# BMS029B_Interface.net
KiCad netlist of a schematic drawn in Altium Designer
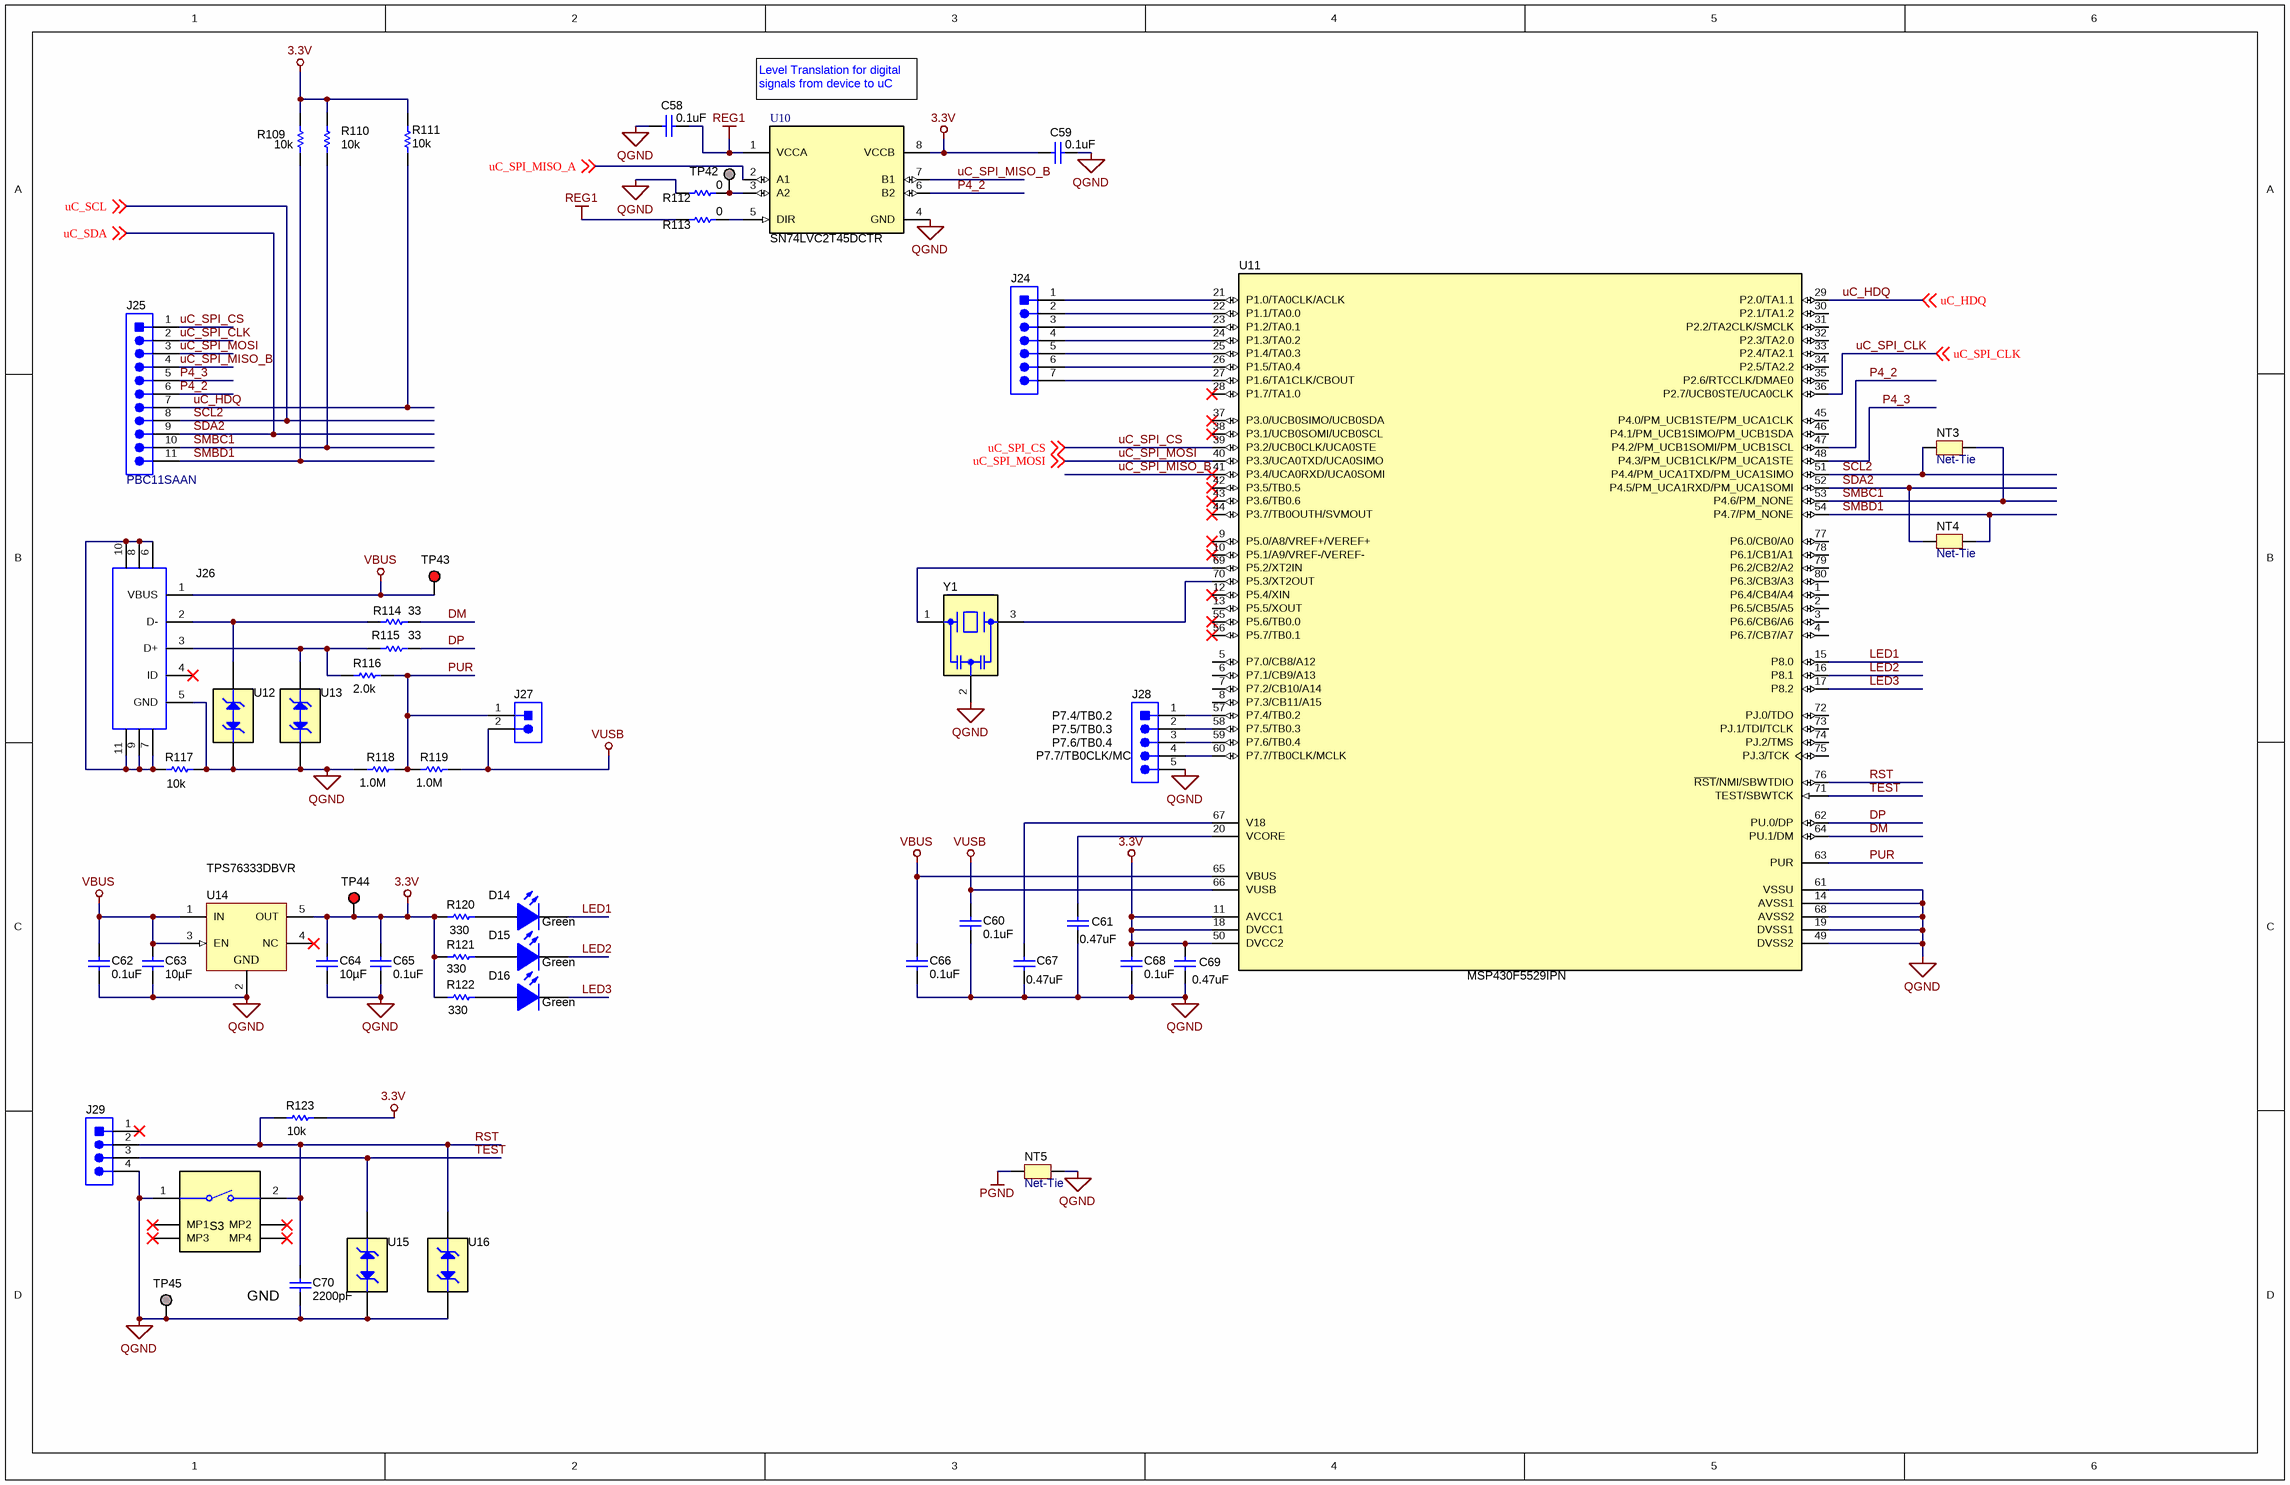
[diagram p0: BMS029B_Interface.SchDoc]

(export (version "E")
  (design (tool "Eeschema 10.0.6"))
  (components
    (comp (ref "C58")
      (value "885012205037")
      (footprint "0402")
      (description "CAP, CERM, 0.1 uF, 16 V, +/- 10%, X7R, 0402")
      (fields
        (field (name "VALUEDISPLAYED") "0.1uF")
        (field (name "MANUFACTURER") "Wurth Elektronik")
        (field (name "PUBLISHER") "Texas Instruments")
      )
      (libsource (lib "Altium Vault - TI") (part "Capacitor"))
    )
    (comp (ref "C59")
      (value "885012205037")
      (footprint "0402")
      (description "CAP, CERM, 0.1 uF, 16 V, +/- 10%, X7R, 0402")
      (fields
        (field (name "VALUEDISPLAYED") "0.1uF")
        (field (name "MANUFACTURER") "Wurth Elektronik")
        (field (name "PUBLISHER") "Texas Instruments")
      )
      (libsource (lib "Altium Vault - TI") (part "Capacitor"))
    )
    (comp (ref "C60")
      (value "885012205037")
      (footprint "0402")
      (description "CAP, CERM, 0.1 uF, 16 V, +/- 10%, X7R, 0402")
      (fields
        (field (name "VALUEDISPLAYED") "0.1uF")
        (field (name "MANUFACTURER") "Wurth Elektronik")
        (field (name "PUBLISHER") "Texas Instruments")
      )
      (libsource (lib "Altium Vault - TI") (part "Capacitor"))
    )
    (comp (ref "C61")
      (value "Capacitor")
      (footprint "0402")
      (description "CAP, CERM, 0.47 uF, 6.3 V, +/- 10%, X5R, 0402")
      (fields
        (field (name "PARTNUMBER") "04026D474KAT2A")
        (field (name "VALUEDISPLAYED") "0.47uF")
        (field (name "MANUFACTURER") "AVX")
        (field (name "PUBLISHER") "Texas Instruments")
      )
      (libsource (lib "Altium Vault - TI") (part "Capacitor"))
    )
    (comp (ref "C62")
      (value "885012205037")
      (footprint "0402")
      (description "CAP, CERM, 0.1 uF, 16 V, +/- 10%, X7R, 0402")
      (fields
        (field (name "VALUEDISPLAYED") "0.1uF")
        (field (name "MANUFACTURER") "Wurth Elektronik")
        (field (name "PUBLISHER") "Texas Instruments")
      )
      (libsource (lib "Altium Vault - TI") (part "Capacitor"))
    )
    (comp (ref "C63")
      (value "CL21A106KOQNNNG")
      (footprint "0805_HV")
      (description "CAP, CERM, 10 µF, 16 V,+/- 10%, X5R, 0805")
      (fields
        (field (name "VALUEDISPLAYED") "10µF")
        (field (name "MANUFACTURER") "Samsung Electro-Mechanics")
      )
      (libsource (lib "Altium Vault - TI") (part "Capacitor"))
    )
    (comp (ref "C64")
      (value "CL21A106KOQNNNG")
      (footprint "0805_HV")
      (description "CAP, CERM, 10 µF, 16 V,+/- 10%, X5R, 0805")
      (fields
        (field (name "VALUEDISPLAYED") "10µF")
        (field (name "MANUFACTURER") "Samsung Electro-Mechanics")
      )
      (libsource (lib "Altium Vault - TI") (part "Capacitor"))
    )
    (comp (ref "C65")
      (value "885012205037")
      (footprint "0402")
      (description "CAP, CERM, 0.1 uF, 16 V, +/- 10%, X7R, 0402")
      (fields
        (field (name "VALUEDISPLAYED") "0.1uF")
        (field (name "MANUFACTURER") "Wurth Elektronik")
        (field (name "PUBLISHER") "Texas Instruments")
      )
      (libsource (lib "Altium Vault - TI") (part "Capacitor"))
    )
    (comp (ref "C66")
      (value "885012205037")
      (footprint "0402")
      (description "CAP, CERM, 0.1 uF, 16 V, +/- 10%, X7R, 0402")
      (fields
        (field (name "VALUEDISPLAYED") "0.1uF")
        (field (name "MANUFACTURER") "Wurth Elektronik")
        (field (name "PUBLISHER") "Texas Instruments")
      )
      (libsource (lib "Altium Vault - TI") (part "Capacitor"))
    )
    (comp (ref "C67")
      (value "Capacitor")
      (footprint "0402")
      (description "CAP, CERM, 0.47 uF, 6.3 V, +/- 10%, X5R, 0402")
      (fields
        (field (name "PARTNUMBER") "04026D474KAT2A")
        (field (name "VALUEDISPLAYED") "0.47uF")
        (field (name "MANUFACTURER") "AVX")
        (field (name "PUBLISHER") "Texas Instruments")
      )
      (libsource (lib "Altium Vault - TI") (part "Capacitor"))
    )
    (comp (ref "C68")
      (value "885012205037")
      (footprint "0402")
      (description "CAP, CERM, 0.1 uF, 16 V, +/- 10%, X7R, 0402")
      (fields
        (field (name "VALUEDISPLAYED") "0.1uF")
        (field (name "MANUFACTURER") "Wurth Elektronik")
        (field (name "PUBLISHER") "Texas Instruments")
      )
      (libsource (lib "Altium Vault - TI") (part "Capacitor"))
    )
    (comp (ref "C69")
      (value "Capacitor")
      (footprint "0402")
      (description "CAP, CERM, 0.47 uF, 6.3 V, +/- 10%, X5R, 0402")
      (fields
        (field (name "PARTNUMBER") "04026D474KAT2A")
        (field (name "VALUEDISPLAYED") "0.47uF")
        (field (name "MANUFACTURER") "AVX")
        (field (name "PUBLISHER") "Texas Instruments")
      )
      (libsource (lib "Altium Vault - TI") (part "Capacitor"))
    )
    (comp (ref "C70")
      (value "885012205008")
      (footprint "0402")
      (description "CAP, CERM, 2200 pF, 10 V, +/- 10%, X7R, 0402")
      (fields
        (field (name "VALUEDISPLAYED") "2200pF")
        (field (name "MANUFACTURER") "Wurth Elektronik")
        (field (name "PUBLISHER") "Texas Instruments")
      )
      (libsource (lib "Altium Vault - TI") (part "Capacitor"))
    )
    (comp (ref "D14")
      (value "Green")
      (footprint "WL-SMCW_GREEN")
      (description "LED, Green, SMD")
      (fields (field (name "MANUFACTURER") "Wurth Elektronik") (field (name "PARTNUMBER") "150060VS75000"))
      (libsource (lib "Altium Vault - TI") (part "CMP-0002894-2"))
    )
    (comp (ref "D15")
      (value "Green")
      (footprint "WL-SMCW_GREEN")
      (description "LED, Green, SMD")
      (fields (field (name "MANUFACTURER") "Wurth Elektronik") (field (name "PARTNUMBER") "150060VS75000"))
      (libsource (lib "Altium Vault - TI") (part "CMP-0002894-2"))
    )
    (comp (ref "D16")
      (value "Green")
      (footprint "WL-SMCW_GREEN")
      (description "LED, Green, SMD")
      (fields (field (name "MANUFACTURER") "Wurth Elektronik") (field (name "PARTNUMBER") "150060VS75000"))
      (libsource (lib "Altium Vault - TI") (part "CMP-0002894-2"))
    )
    (comp (ref "J24")
      (value "PBC07SAAN")
      (footprint "Sullins_xxC07SAAN")
      (description "Header, 2.54 mm, 7x1, Gold, TH")
      (fields
        (field (name "MANUFACTURER") "Sullins Connector Solutions")
        (field (name "PUBLISHER") "Texas Instruments")
      )
      (libsource (lib "Altium Vault - TI") (part "CMP-0054584-1"))
    )
    (comp (ref "J25")
      (value "PBC11SAAN")
      (footprint "Sullins_xxC11SAAN")
      (description "Header, 2.54 mm, 11x1, Gold, TH")
      (fields
        (field (name "MANUFACTURER") "Sullins Connector Solutions")
        (field (name "PUBLISHER") "Texas Instruments")
      )
      (libsource (lib "Altium Vault - TI") (part "Header_11x1"))
    )
    (comp (ref "J26")
      (value "CONN_USB_5Pos-6Shld")
      (footprint "Molex_47346-1001")
      (description "Receptacle, Micro-USB Type B, 0.65 mm, 5x1, R/A, Bottom Mount SMT")
      (fields
        (field (name "PARTNUMBER") "47346-1001")
        (field (name "MANUFACTURER") "Molex")
        (field (name "SYMBOLCREATOR") "a0411947")
        (field (name "PUBLISHER") "Texas Instruments")
      )
      (libsource (lib "Altium Vault - TI") (part "CONN_USB_5Pos-6Shld"))
    )
    (comp (ref "J27")
      (value "61300211121")
      (footprint "WURTH_61300211121")
      (description "Header, 2.54 mm, 2x1, Gold, TH")
      (fields (field (name "MANUFACTURER") "Wurth Elektronik"))
      (libsource (lib "Altium Vault - TI") (part "CMP-0054794-2"))
    )
    (comp (ref "J28")
      (value "PEC05SAAN")
      (footprint "Sullins_PxC05SAAN")
      (description "Header, 2.54mm, 5x1, Tin, TH")
      (fields
        (field (name "MANUFACTURER") "Sullins Connector Solutions")
        (field (name "PUBLISHER") "Texas Instruments")
      )
      (libsource (lib "Altium Vault - TI") (part "CMP-0054597-1"))
    )
    (comp (ref "J29")
      (value "22284043")
      (footprint "Molex_0022284043")
      (description "Header, 2.54mm, 4x1, Tin, TH")
      (fields (field (name "MANUFACTURER") "Molex") (field (name "PUBLISHER") "Texas Instruments"))
      (libsource (lib "Altium Vault - TI") (part "CMP-0055331-1"))
    )
    (comp (ref "NT3")
      (value "Net-Tie")
      (footprint "Net-Tie_10mil")
      (description "Single point connection between nets.")
      (libsource (lib "Altium Vault - TI") (part "Net-Tie"))
    )
    (comp (ref "NT4")
      (value "Net-Tie")
      (footprint "Net-Tie_10mil")
      (description "Single point connection between nets.")
      (libsource (lib "Altium Vault - TI") (part "Net-Tie"))
    )
    (comp (ref "NT5")
      (value "Net-Tie")
      (footprint "Net-Tie_0805_HV_NoOverlay")
      (description "Single point connection between nets.")
      (libsource (lib "") (part "Net-Tie_1"))
    )
    (comp (ref "R109")
      (value "CRCW060310K0JNEA")
      (footprint "0603")
      (description "RES, 10 k, 5%, 0.1 W, AEC-Q200 Grade 0, 0603")
      (fields (field (name "MANUFACTURER") "Vishay-Dale") (field (name "VALUEDISPLAYED") "10k"))
      (libsource (lib "Altium Vault - TI") (part "Resistor"))
    )
    (comp (ref "R110")
      (value "CRCW060310K0JNEA")
      (footprint "0603")
      (description "RES, 10 k, 5%, 0.1 W, AEC-Q200 Grade 0, 0603")
      (fields (field (name "MANUFACTURER") "Vishay-Dale") (field (name "VALUEDISPLAYED") "10k"))
      (libsource (lib "Altium Vault - TI") (part "CMP-0025701-4"))
    )
    (comp (ref "R111")
      (value "CRCW060310K0JNEA")
      (footprint "0603")
      (description "RES, 10 k, 5%, 0.1 W, AEC-Q200 Grade 0, 0603")
      (fields (field (name "MANUFACTURER") "Vishay-Dale") (field (name "VALUEDISPLAYED") "10k"))
      (libsource (lib "Altium Vault - TI") (part "Resistor"))
    )
    (comp (ref "R112")
      (value "CRCW06030000Z0EA")
      (footprint "0603")
      (description "RES, 0, 5%, 0.1 W, AEC-Q200 Grade 0, 0603")
      (fields (field (name "MANUFACTURER") "Vishay-Dale") (field (name "VALUEDISPLAYED") "0"))
      (libsource (lib "Altium Vault - TI") (part "Resistor"))
    )
    (comp (ref "R113")
      (value "CRCW06030000Z0EA")
      (footprint "0603")
      (description "RES, 0, 5%, 0.1 W, AEC-Q200 Grade 0, 0603")
      (fields (field (name "MANUFACTURER") "Vishay-Dale") (field (name "VALUEDISPLAYED") "0"))
      (libsource (lib "Altium Vault - TI") (part "Resistor"))
    )
    (comp (ref "R114")
      (value "Resistor")
      (footprint "0402")
      (description "RES, 33, 5%, 0.063 W, AEC-Q200 Grade 0, 0402")
      (fields
        (field (name "PARTNUMBER") "CRCW040233R0JNED")
        (field (name "VALUEDISPLAYED") "33")
        (field (name "MANUFACTURER") "Vishay-Dale")
        (field (name "PUBLISHER") "Texas Instruments")
      )
      (libsource (lib "Altium Vault - TI") (part "Resistor"))
    )
    (comp (ref "R115")
      (value "Resistor")
      (footprint "0402")
      (description "RES, 33, 5%, 0.063 W, AEC-Q200 Grade 0, 0402")
      (fields
        (field (name "PARTNUMBER") "CRCW040233R0JNED")
        (field (name "VALUEDISPLAYED") "33")
        (field (name "MANUFACTURER") "Vishay-Dale")
        (field (name "PUBLISHER") "Texas Instruments")
      )
      (libsource (lib "Altium Vault - TI") (part "Resistor"))
    )
    (comp (ref "R116")
      (value "Resistor")
      (footprint "0402")
      (description "RES, 2.0 k, 5%, 0.063 W, AEC-Q200 Grade 0, 0402")
      (fields
        (field (name "PARTNUMBER") "CRCW04022K00JNED")
        (field (name "VALUEDISPLAYED") "2.0k")
        (field (name "MANUFACTURER") "Vishay-Dale")
        (field (name "PUBLISHER") "Texas Instruments")
      )
      (libsource (lib "Altium Vault - TI") (part "Resistor"))
    )
    (comp (ref "R117")
      (value "Resistor")
      (footprint "0402")
      (description "RES, 10 k, 5%, 0.063 W, AEC-Q200 Grade 0, 0402")
      (fields
        (field (name "PARTNUMBER") "CRCW040210K0JNED")
        (field (name "VALUEDISPLAYED") "10k")
        (field (name "MANUFACTURER") "Vishay-Dale")
        (field (name "PUBLISHER") "Texas Instruments")
      )
      (libsource (lib "Altium Vault - TI") (part "Resistor"))
    )
    (comp (ref "R118")
      (value "Resistor")
      (footprint "0402")
      (description "RES, 1.0 M, 5%, 0.063 W, AEC-Q200 Grade 0, 0402")
      (fields
        (field (name "PARTNUMBER") "CRCW04021M00JNED")
        (field (name "VALUEDISPLAYED") "1.0M")
        (field (name "MANUFACTURER") "Vishay-Dale")
        (field (name "PUBLISHER") "Texas Instruments")
      )
      (libsource (lib "Altium Vault - TI") (part "Resistor"))
    )
    (comp (ref "R119")
      (value "Resistor")
      (footprint "0402")
      (description "RES, 1.0 M, 5%, 0.063 W, AEC-Q200 Grade 0, 0402")
      (fields
        (field (name "PARTNUMBER") "CRCW04021M00JNED")
        (field (name "VALUEDISPLAYED") "1.0M")
        (field (name "MANUFACTURER") "Vishay-Dale")
        (field (name "PUBLISHER") "Texas Instruments")
      )
      (libsource (lib "Altium Vault - TI") (part "Resistor"))
    )
    (comp (ref "R120")
      (value "Resistor")
      (footprint "0402")
      (description "RES, 330, 1%, 0.1 W, AEC-Q200 Grade 0, 0402")
      (fields
        (field (name "PARTNUMBER") "ERJ-2RKF3300X")
        (field (name "VALUEDISPLAYED") "330")
        (field (name "MANUFACTURER") "Panasonic")
        (field (name "PUBLISHER") "Texas Instruments")
      )
      (libsource (lib "Altium Vault - TI") (part "Resistor"))
    )
    (comp (ref "R121")
      (value "Resistor")
      (footprint "0402")
      (description "RES, 330, 1%, 0.1 W, AEC-Q200 Grade 0, 0402")
      (fields
        (field (name "PARTNUMBER") "ERJ-2RKF3300X")
        (field (name "VALUEDISPLAYED") "330")
        (field (name "MANUFACTURER") "Panasonic")
        (field (name "PUBLISHER") "Texas Instruments")
      )
      (libsource (lib "Altium Vault - TI") (part "Resistor"))
    )
    (comp (ref "R122")
      (value "Resistor")
      (footprint "0402")
      (description "RES, 330, 1%, 0.1 W, AEC-Q200 Grade 0, 0402")
      (fields
        (field (name "PARTNUMBER") "ERJ-2RKF3300X")
        (field (name "VALUEDISPLAYED") "330")
        (field (name "MANUFACTURER") "Panasonic")
        (field (name "PUBLISHER") "Texas Instruments")
      )
      (libsource (lib "Altium Vault - TI") (part "Resistor"))
    )
    (comp (ref "R123")
      (value "Resistor")
      (footprint "0402")
      (description "RES, 10 k, 5%, 0.063 W, AEC-Q200 Grade 0, 0402")
      (fields
        (field (name "PARTNUMBER") "CRCW040210K0JNED")
        (field (name "VALUEDISPLAYED") "10k")
        (field (name "MANUFACTURER") "Vishay-Dale")
        (field (name "PUBLISHER") "Texas Instruments")
      )
      (libsource (lib "Altium Vault - TI") (part "Resistor"))
    )
    (comp (ref "S3")
      (value "PTS820 J20M SMTR LFS")
      (footprint "SW_PTS820")
      (description "Switch, SPST-NO,  Off-Mom, 0.05A, 12VDC, SMD")
      (fields (field (name "MANUFACTURER") "C&K Components") (field (name "PUBLISHER") "Texas Instruments"))
      (libsource (lib "Altium Vault - TI") (part "SW_SPST_12_4MP"))
    )
    (comp (ref "TP42")
      (value "TESTPOINT")
      (footprint "TP_50MIL-25MILHOLE")
      (description "TEST POINT.  No entry in BOM.")
      (libsource (lib "Altium Vault - TI") (part "TESTPOINT"))
    )
    (comp (ref "TP43")
      (value "5005")
      (footprint "Keystone5005")
      (description "Test Point, Compact, Red, TH")
      (fields (field (name "MANUFACTURER") "Keystone") (field (name "PUBLISHER") "Texas Instruments"))
      (libsource (lib "Altium Vault - TI") (part "5005"))
    )
    (comp (ref "TP44")
      (value "5005")
      (footprint "Keystone5005")
      (description "Test Point, Compact, Red, TH")
      (fields (field (name "MANUFACTURER") "Keystone") (field (name "PUBLISHER") "Texas Instruments"))
      (libsource (lib "Altium Vault - TI") (part "5005"))
    )
    (comp (ref "TP45")
      (value "TESTPOINT")
      (footprint "TP_SM_1MM")
      (description "1mm Test Point, SMT")
      (fields
        (field (name "PARTNUMBER") "TP_SM_1MM")
        (field (name "MANUFACTURER") "Any")
        (field (name "PUBLISHER") "Texas Instruments")
      )
      (libsource (lib "Altium Vault - TI") (part "TESTPOINT"))
    )
    (comp (ref "U10")
      (value "SN74LVC2T45DCTR")
      (footprint "DCT0008A_N")
      (fields
        (field (name "MANUFACTURER") "Texas Instruments")
        (field (name "GENERIC PART NUMBER") "SN74LVC2T45")
        (field (name "PARTNUMBER") "SN74LVC2T45DCTR")
      )
      (libsource (lib "Altium Vault - TI") (part "TI-SN74XVC2T45-8"))
    )
    (comp (ref "U11")
      (value "CMP-0038965-1")
      (footprint "PN0080A_N")
      (fields (field (name "PARTNUMBER") "MSP430F5529IPN") (field (name "MANUFACTURER") "Texas Instruments"))
      (libsource (lib "Altium Vault - TI") (part "TI-MSP430F552X_A-PN80"))
    )
    (comp (ref "U12")
      (value "TPD1E10B06DPYT")
      (footprint "DPY0002A")
      (description "Single-Channel ESD in 0402 Package With 10pF Capacitance and 6V Breakdown, DPY0002A (X1SON-2)")
      (fields
        (field (name "MANUFACTURER") "Texas Instruments")
        (field (name "ALTERNATE PARTNUMBER") "TPD1E10B06DPYR")
      )
      (libsource (lib "Altium Vault - TI") (part "CMP-0043094-3"))
    )
    (comp (ref "U13")
      (value "TPD1E10B06DPYT")
      (footprint "DPY0002A")
      (description "Single-Channel ESD in 0402 Package With 10pF Capacitance and 6V Breakdown, DPY0002A (X1SON-2)")
      (fields
        (field (name "MANUFACTURER") "Texas Instruments")
        (field (name "ALTERNATE PARTNUMBER") "TPD1E10B06DPYR")
      )
      (libsource (lib "Altium Vault - TI") (part "CMP-0043094-3"))
    )
    (comp (ref "U14")
      (value "CMP-0035539-1")
      (footprint "DBV0005A_N")
      (fields (field (name "MANUFACTURER") "Texas Instruments") (field (name "PARTNUMBER") "TPS76333DBVR"))
      (libsource (lib "Altium Vault - TI") (part "CMP-0035539-1"))
    )
    (comp (ref "U15")
      (value "TPD1E10B06DPYT")
      (footprint "DPY0002A")
      (description "Single-Channel ESD in 0402 Package With 10pF Capacitance and 6V Breakdown, DPY0002A (X1SON-2)")
      (fields
        (field (name "MANUFACTURER") "Texas Instruments")
        (field (name "ALTERNATE PARTNUMBER") "TPD1E10B06DPYR")
      )
      (libsource (lib "Altium Vault - TI") (part "CMP-0043094-3"))
    )
    (comp (ref "U16")
      (value "TPD1E10B06DPYT")
      (footprint "DPY0002A")
      (description "Single-Channel ESD in 0402 Package With 10pF Capacitance and 6V Breakdown, DPY0002A (X1SON-2)")
      (fields
        (field (name "MANUFACTURER") "Texas Instruments")
        (field (name "ALTERNATE PARTNUMBER") "TPD1E10B06DPYR")
      )
      (libsource (lib "Altium Vault - TI") (part "CMP-0043094-3"))
    )
    (comp (ref "Y1")
      (value "CSTCR4M00G55B-R0")
      (footprint "Murata_CSTCR_G")
      (description "Resonator, 4 MHz, 39 pF, AEC-Q200 Grade 1, SMD")
      (fields (field (name "MANUFACTURER") "MuRata"))
      (libsource (lib "Altium Vault - TI") (part "CMP-0084387-1"))
    )
  )
  (nets
    (net (code "2") (name "/DM") (class "Default")
      (node (ref "R114") (pin "2") (pinfunction "2_2") (pintype "passive"))
      (node (ref "U11") (pin "64") (pinfunction "PU.1/DM_64") (pintype "bidirectional"))
    )
    (net (code "3") (name "/DP") (class "Default")
      (node (ref "R115") (pin "2") (pinfunction "2_2") (pintype "passive"))
      (node (ref "U11") (pin "62") (pinfunction "PU.0/DP_62") (pintype "bidirectional"))
    )
    (net (code "4") (name "/LED1") (class "Default")
      (node (ref "D14") (pin "1") (pinfunction "K_1") (pintype "passive"))
      (node (ref "U11") (pin "15") (pinfunction "P8.0_15") (pintype "bidirectional"))
    )
    (net (code "5") (name "/LED2") (class "Default")
      (node (ref "D15") (pin "1") (pinfunction "K_1") (pintype "passive"))
      (node (ref "U11") (pin "16") (pinfunction "P8.1_16") (pintype "bidirectional"))
    )
    (net (code "6") (name "/LED3") (class "Default")
      (node (ref "D16") (pin "1") (pinfunction "K_1") (pintype "passive"))
      (node (ref "U11") (pin "17") (pinfunction "P8.2_17") (pintype "bidirectional"))
    )
    (net (code "7") (name "/P4_2") (class "Default")
      (node (ref "J25") (pin "6") (pinfunction "6_6") (pintype "passive"))
      (node (ref "U10") (pin "6") (pinfunction "B2_6") (pintype "bidirectional"))
      (node (ref "U11") (pin "47") (pinfunction "P4.2/PM_UCB1SOMI/PM_UCB1SCL_47") (pintype "bidirectional"))
    )
    (net (code "8") (name "/P4_3") (class "Default")
      (node (ref "J25") (pin "5") (pinfunction "5_5") (pintype "passive"))
      (node (ref "U11") (pin "48") (pinfunction "P4.3/PM_UCB1CLK/PM_UCA1STE_48") (pintype "bidirectional"))
    )
    (net (code "9") (name "/PUR") (class "Default")
      (node (ref "J27") (pin "1") (pinfunction "1_1") (pintype "passive"))
      (node (ref "R116") (pin "1") (pinfunction "1_1") (pintype "passive"))
      (node (ref "R118") (pin "2") (pinfunction "2_2") (pintype "passive"))
      (node (ref "R119") (pin "1") (pinfunction "1_1") (pintype "passive"))
      (node (ref "U11") (pin "63") (pinfunction "PUR_63") (pintype "passive"))
    )
    (net (code "10") (name "/RST") (class "Default")
      (node (ref "C70") (pin "1") (pinfunction "1_1") (pintype "passive"))
      (node (ref "J29") (pin "2") (pinfunction "2_2") (pintype "passive"))
      (node (ref "R123") (pin "1") (pinfunction "1_1") (pintype "passive"))
      (node (ref "S3") (pin "2") (pinfunction "2_2") (pintype "passive"))
      (node (ref "U11") (pin "76") (pinfunction "~{RST}/NMI/SBWTDIO_76") (pintype "bidirectional"))
      (node (ref "U16") (pin "1") (pinfunction "K_1") (pintype "passive"))
    )
    (net (code "11") (name "/SMBC1") (class "Default")
      (node (ref "J25") (pin "10") (pinfunction "10_10") (pintype "passive"))
      (node (ref "NT3") (pin "2") (pinfunction "2_2") (pintype "passive"))
      (node (ref "R110") (pin "2") (pinfunction "2_2") (pintype "passive"))
      (node (ref "U11") (pin "53") (pinfunction "P4.6/PM_NONE_53") (pintype "bidirectional"))
    )
    (net (code "12") (name "/SMBD1") (class "Default")
      (node (ref "J25") (pin "11") (pinfunction "11_11") (pintype "passive"))
      (node (ref "NT4") (pin "2") (pinfunction "2_2") (pintype "passive"))
      (node (ref "R109") (pin "2") (pinfunction "2_2") (pintype "passive"))
      (node (ref "U11") (pin "54") (pinfunction "P4.7/PM_NONE_54") (pintype "bidirectional"))
    )
    (net (code "13") (name "/TEST") (class "Default")
      (node (ref "J29") (pin "3") (pinfunction "3_3") (pintype "passive"))
      (node (ref "U11") (pin "71") (pinfunction "TEST/SBWTCK_71") (pintype "input"))
      (node (ref "U15") (pin "1") (pinfunction "K_1") (pintype "passive"))
    )
    (net (code "14") (name "/uC_SPI_MISO_B") (class "Default")
      (node (ref "J25") (pin "4") (pinfunction "4_4") (pintype "passive"))
      (node (ref "U10") (pin "7") (pinfunction "B1_7") (pintype "bidirectional"))
      (node (ref "U11") (pin "41") (pinfunction "P3.4/UCA0RXD/UCA0SOMI_41") (pintype "bidirectional"))
    )
    (net (code "15") (name "3.3V") (class "Default")
      (node (ref "C59") (pin "2") (pinfunction "2_2") (pintype "passive"))
      (node (ref "C64") (pin "1") (pinfunction "1_1") (pintype "passive"))
      (node (ref "C65") (pin "1") (pinfunction "1_1") (pintype "passive"))
      (node (ref "C68") (pin "1") (pinfunction "1_1") (pintype "passive"))
      (node (ref "C69") (pin "1") (pinfunction "1_1") (pintype "passive"))
      (node (ref "R109") (pin "1") (pinfunction "1_1") (pintype "passive"))
      (node (ref "R110") (pin "1") (pinfunction "1_1") (pintype "passive"))
      (node (ref "R111") (pin "1") (pinfunction "1_1") (pintype "passive"))
      (node (ref "R120") (pin "2") (pinfunction "2_2") (pintype "passive"))
      (node (ref "R121") (pin "2") (pinfunction "2_2") (pintype "passive"))
      (node (ref "R122") (pin "2") (pinfunction "2_2") (pintype "passive"))
      (node (ref "R123") (pin "2") (pinfunction "2_2") (pintype "passive"))
      (node (ref "TP44") (pin "1") (pintype "passive"))
      (node (ref "U10") (pin "8") (pinfunction "VCCB_8") (pintype "power_in"))
      (node (ref "U11") (pin "11") (pinfunction "AVCC1_11") (pintype "power_in"))
      (node (ref "U11") (pin "18") (pinfunction "DVCC1_18") (pintype "power_in"))
      (node (ref "U11") (pin "50") (pinfunction "DVCC2_50") (pintype "power_in"))
      (node (ref "U14") (pin "5") (pinfunction "OUT_5") (pintype "power_in"))
    )
    (net (code "16") (name "Net-(D14-A)") (class "Default")
      (node (ref "D14") (pin "2") (pinfunction "A_2") (pintype "passive"))
      (node (ref "R120") (pin "1") (pinfunction "1_1") (pintype "passive"))
    )
    (net (code "17") (name "Net-(D15-A)") (class "Default")
      (node (ref "D15") (pin "2") (pinfunction "A_2") (pintype "passive"))
      (node (ref "R121") (pin "1") (pinfunction "1_1") (pintype "passive"))
    )
    (net (code "18") (name "Net-(D16-A)") (class "Default")
      (node (ref "D16") (pin "2") (pinfunction "A_2") (pintype "passive"))
      (node (ref "R122") (pin "1") (pinfunction "1_1") (pintype "passive"))
    )
    (net (code "19") (name "Net-(J26-D+)") (class "Default")
      (node (ref "J26") (pin "3") (pinfunction "D+_3") (pintype "passive"))
      (node (ref "R115") (pin "1") (pinfunction "1_1") (pintype "passive"))
      (node (ref "R116") (pin "2") (pinfunction "2_2") (pintype "passive"))
      (node (ref "U13") (pin "1") (pinfunction "K_1") (pintype "passive"))
    )
    (net (code "20") (name "Net-(J26-D-)") (class "Default")
      (node (ref "J26") (pin "2") (pinfunction "D-_2") (pintype "passive"))
      (node (ref "R114") (pin "1") (pinfunction "1_1") (pintype "passive"))
      (node (ref "U12") (pin "1") (pinfunction "K_1") (pintype "passive"))
    )
    (net (code "21") (name "Net-(J26-Pad10)") (class "Default")
      (node (ref "J26") (pin "10") (pinfunction "10_10") (pintype "passive"))
      (node (ref "J26") (pin "11") (pinfunction "11_11") (pintype "passive"))
      (node (ref "J26") (pin "6") (pinfunction "6_6") (pintype "passive"))
      (node (ref "J26") (pin "7") (pinfunction "7_7") (pintype "passive"))
      (node (ref "J26") (pin "8") (pinfunction "8_8") (pintype "passive"))
      (node (ref "J26") (pin "9") (pinfunction "9_9") (pintype "passive"))
      (node (ref "R117") (pin "2") (pinfunction "2_2") (pintype "passive"))
    )
    (net (code "22") (name "Net-(U10-A2)") (class "Default")
      (node (ref "R112") (pin "2") (pinfunction "2_2") (pintype "passive"))
      (node (ref "TP42") (pin "1") (pintype "passive"))
      (node (ref "U10") (pin "3") (pinfunction "A2_3") (pintype "bidirectional"))
    )
    (net (code "23") (name "Net-(U10-DIR)") (class "Default")
      (node (ref "R113") (pin "2") (pinfunction "2_2") (pintype "passive"))
      (node (ref "U10") (pin "5") (pinfunction "DIR_5") (pintype "input"))
    )
    (net (code "24") (name "Net-(U11-P1.0{slash}TA0CLK{slash}ACLK)") (class "Default")
      (node (ref "J24") (pin "1") (pinfunction "1_1") (pintype "passive"))
      (node (ref "U11") (pin "21") (pinfunction "P1.0/TA0CLK/ACLK_21") (pintype "bidirectional"))
    )
    (net (code "25") (name "Net-(U11-P1.1{slash}TA0.0)") (class "Default")
      (node (ref "J24") (pin "2") (pinfunction "2_2") (pintype "passive"))
      (node (ref "U11") (pin "22") (pinfunction "P1.1/TA0.0_22") (pintype "bidirectional"))
    )
    (net (code "26") (name "Net-(U11-P1.2{slash}TA0.1)") (class "Default")
      (node (ref "J24") (pin "3") (pinfunction "3_3") (pintype "passive"))
      (node (ref "U11") (pin "23") (pinfunction "P1.2/TA0.1_23") (pintype "bidirectional"))
    )
    (net (code "27") (name "Net-(U11-P1.3{slash}TA0.2)") (class "Default")
      (node (ref "J24") (pin "4") (pinfunction "4_4") (pintype "passive"))
      (node (ref "U11") (pin "24") (pinfunction "P1.3/TA0.2_24") (pintype "bidirectional"))
    )
    (net (code "28") (name "Net-(U11-P1.4{slash}TA0.3)") (class "Default")
      (node (ref "J24") (pin "5") (pinfunction "5_5") (pintype "passive"))
      (node (ref "U11") (pin "25") (pinfunction "P1.4/TA0.3_25") (pintype "bidirectional"))
    )
    (net (code "29") (name "Net-(U11-P1.5{slash}TA0.4)") (class "Default")
      (node (ref "J24") (pin "6") (pinfunction "6_6") (pintype "passive"))
      (node (ref "U11") (pin "26") (pinfunction "P1.5/TA0.4_26") (pintype "bidirectional"))
    )
    (net (code "30") (name "Net-(U11-P1.6{slash}TA1CLK{slash}CBOUT)") (class "Default")
      (node (ref "J24") (pin "7") (pinfunction "7_7") (pintype "passive"))
      (node (ref "U11") (pin "27") (pinfunction "P1.6/TA1CLK/CBOUT_27") (pintype "bidirectional"))
    )
    (net (code "31") (name "Net-(U11-P5.2{slash}XT2IN)") (class "Default")
      (node (ref "U11") (pin "69") (pinfunction "P5.2/XT2IN_69") (pintype "bidirectional"))
      (node (ref "Y1") (pin "1") (pinfunction "In_1") (pintype "passive"))
    )
    (net (code "32") (name "Net-(U11-P5.3{slash}XT2OUT)") (class "Default")
      (node (ref "U11") (pin "70") (pinfunction "P5.3/XT2OUT_70") (pintype "bidirectional"))
      (node (ref "Y1") (pin "3") (pinfunction "Out_3") (pintype "passive"))
    )
    (net (code "33") (name "Net-(U11-P7.4{slash}TB0.2)") (class "Default")
      (node (ref "J28") (pin "1") (pinfunction "1_1") (pintype "passive"))
      (node (ref "U11") (pin "57") (pinfunction "P7.4/TB0.2_57") (pintype "bidirectional"))
    )
    (net (code "34") (name "Net-(U11-P7.5{slash}TB0.3)") (class "Default")
      (node (ref "J28") (pin "2") (pinfunction "2_2") (pintype "passive"))
      (node (ref "U11") (pin "58") (pinfunction "P7.5/TB0.3_58") (pintype "bidirectional"))
    )
    (net (code "35") (name "Net-(U11-P7.6{slash}TB0.4)") (class "Default")
      (node (ref "J28") (pin "3") (pinfunction "3_3") (pintype "passive"))
      (node (ref "U11") (pin "59") (pinfunction "P7.6/TB0.4_59") (pintype "bidirectional"))
    )
    (net (code "36") (name "Net-(U11-P7.7{slash}TB0CLK{slash}MCLK)") (class "Default")
      (node (ref "J28") (pin "4") (pinfunction "4_4") (pintype "passive"))
      (node (ref "U11") (pin "60") (pinfunction "P7.7/TB0CLK/MCLK_60") (pintype "bidirectional"))
    )
    (net (code "37") (name "Net-(U11-V18)") (class "Default")
      (node (ref "C67") (pin "1") (pinfunction "1_1") (pintype "passive"))
      (node (ref "U11") (pin "67") (pinfunction "V18_67") (pintype "passive"))
    )
    (net (code "38") (name "Net-(U11-VCORE)") (class "Default")
      (node (ref "C61") (pin "1") (pinfunction "1_1") (pintype "passive"))
      (node (ref "U11") (pin "20") (pinfunction "VCORE_20") (pintype "passive"))
    )
    (net (code "39") (name "PGND") (class "Default")
      (node (ref "NT5") (pin "2") (pinfunction "2_2") (pintype "passive"))
    )
    (net (code "40") (name "QGND") (class "Default")
      (node (ref "C58") (pin "1") (pinfunction "1_1") (pintype "passive"))
      (node (ref "C59") (pin "1") (pinfunction "1_1") (pintype "passive"))
      (node (ref "C60") (pin "2") (pinfunction "2_2") (pintype "passive"))
      (node (ref "C61") (pin "2") (pinfunction "2_2") (pintype "passive"))
      (node (ref "C62") (pin "2") (pinfunction "2_2") (pintype "passive"))
      (node (ref "C63") (pin "2") (pinfunction "2_2") (pintype "passive"))
      (node (ref "C64") (pin "2") (pinfunction "2_2") (pintype "passive"))
      (node (ref "C65") (pin "2") (pinfunction "2_2") (pintype "passive"))
      (node (ref "C66") (pin "2") (pinfunction "2_2") (pintype "passive"))
      (node (ref "C67") (pin "2") (pinfunction "2_2") (pintype "passive"))
      (node (ref "C68") (pin "2") (pinfunction "2_2") (pintype "passive"))
      (node (ref "C69") (pin "2") (pinfunction "2_2") (pintype "passive"))
      (node (ref "C70") (pin "2") (pinfunction "2_2") (pintype "passive"))
      (node (ref "J26") (pin "5") (pinfunction "GND_5") (pintype "passive"))
      (node (ref "J28") (pin "5") (pinfunction "5_5") (pintype "passive"))
      (node (ref "J29") (pin "4") (pinfunction "4_4") (pintype "passive"))
      (node (ref "NT5") (pin "1") (pinfunction "1_1") (pintype "passive"))
      (node (ref "R112") (pin "1") (pinfunction "1_1") (pintype "passive"))
      (node (ref "R117") (pin "1") (pinfunction "1_1") (pintype "passive"))
      (node (ref "R118") (pin "1") (pinfunction "1_1") (pintype "passive"))
      (node (ref "S3") (pin "1") (pinfunction "1_1") (pintype "passive"))
      (node (ref "TP45") (pin "1") (pintype "passive"))
      (node (ref "U10") (pin "4") (pinfunction "GND_4") (pintype "power_in"))
      (node (ref "U11") (pin "14") (pinfunction "AVSS1_14") (pintype "power_in"))
      (node (ref "U11") (pin "19") (pinfunction "DVSS1_19") (pintype "power_in"))
      (node (ref "U11") (pin "49") (pinfunction "DVSS2_49") (pintype "power_in"))
      (node (ref "U11") (pin "61") (pinfunction "VSSU_61") (pintype "power_in"))
      (node (ref "U11") (pin "68") (pinfunction "AVSS2_68") (pintype "power_in"))
      (node (ref "U12") (pin "2") (pinfunction "A_2") (pintype "passive"))
      (node (ref "U13") (pin "2") (pinfunction "A_2") (pintype "passive"))
      (node (ref "U14") (pin "2") (pinfunction "GND_2") (pintype "power_in"))
      (node (ref "U15") (pin "2") (pinfunction "A_2") (pintype "passive"))
      (node (ref "U16") (pin "2") (pinfunction "A_2") (pintype "passive"))
      (node (ref "Y1") (pin "2") (pinfunction "GND_2") (pintype "passive"))
    )
    (net (code "41") (name "REG1") (class "Default")
      (node (ref "C58") (pin "2") (pinfunction "2_2") (pintype "passive"))
      (node (ref "R113") (pin "1") (pinfunction "1_1") (pintype "passive"))
      (node (ref "U10") (pin "1") (pinfunction "VCCA_1") (pintype "power_in"))
    )
    (net (code "42") (name "VBUS") (class "Default")
      (node (ref "C62") (pin "1") (pinfunction "1_1") (pintype "passive"))
      (node (ref "C63") (pin "1") (pinfunction "1_1") (pintype "passive"))
      (node (ref "C66") (pin "1") (pinfunction "1_1") (pintype "passive"))
      (node (ref "J26") (pin "1") (pinfunction "VBUS_1") (pintype "passive"))
      (node (ref "TP43") (pin "1") (pintype "passive"))
      (node (ref "U11") (pin "65") (pinfunction "VBUS_65") (pintype "power_in"))
      (node (ref "U14") (pin "1") (pinfunction "IN_1") (pintype "power_in"))
      (node (ref "U14") (pin "3") (pinfunction "EN_3") (pintype "input"))
    )
    (net (code "43") (name "VUSB") (class "Default")
      (node (ref "C60") (pin "1") (pinfunction "1_1") (pintype "passive"))
      (node (ref "J27") (pin "2") (pinfunction "2_2") (pintype "passive"))
      (node (ref "R119") (pin "2") (pinfunction "2_2") (pintype "passive"))
      (node (ref "U11") (pin "66") (pinfunction "VUSB_66") (pintype "power_in"))
    )
    (net (code "44") (name "uC_HDQ") (class "Default")
      (node (ref "J25") (pin "7") (pinfunction "7_7") (pintype "passive"))
      (node (ref "R111") (pin "2") (pinfunction "2_2") (pintype "passive"))
      (node (ref "U11") (pin "29") (pinfunction "P2.0/TA1.1_29") (pintype "bidirectional"))
    )
    (net (code "45") (name "uC_SCL") (class "Default")
      (node (ref "J25") (pin "8") (pinfunction "8_8") (pintype "passive"))
      (node (ref "NT3") (pin "1") (pinfunction "1_1") (pintype "passive"))
      (node (ref "U11") (pin "51") (pinfunction "P4.4/PM_UCA1TXD/PM_UCA1SIMO_51") (pintype "bidirectional"))
    )
    (net (code "46") (name "uC_SDA") (class "Default")
      (node (ref "J25") (pin "9") (pinfunction "9_9") (pintype "passive"))
      (node (ref "NT4") (pin "1") (pinfunction "1_1") (pintype "passive"))
      (node (ref "U11") (pin "52") (pinfunction "P4.5/PM_UCA1RXD/PM_UCA1SOMI_52") (pintype "bidirectional"))
    )
    (net (code "47") (name "uC_SPI_CLK") (class "Default")
      (node (ref "J25") (pin "2") (pinfunction "2_2") (pintype "passive"))
      (node (ref "U11") (pin "36") (pinfunction "P2.7/UCB0STE/UCA0CLK_36") (pintype "bidirectional"))
    )
    (net (code "48") (name "uC_SPI_CS") (class "Default")
      (node (ref "J25") (pin "1") (pinfunction "1_1") (pintype "passive"))
      (node (ref "U11") (pin "39") (pinfunction "P3.2/UCB0CLK/UCA0STE_39") (pintype "bidirectional"))
    )
    (net (code "49") (name "uC_SPI_MISO_A") (class "Default")
      (node (ref "U10") (pin "2") (pinfunction "A1_2") (pintype "bidirectional"))
    )
    (net (code "50") (name "uC_SPI_MOSI") (class "Default")
      (node (ref "J25") (pin "3") (pinfunction "3_3") (pintype "passive"))
      (node (ref "U11") (pin "40") (pinfunction "P3.3/UCA0TXD/UCA0SIMO_40") (pintype "bidirectional"))
    )
    (net (code "51") (name "unconnected-(J26-ID-Pad4)") (class "Default")
      (node (ref "J26") (pin "4") (pinfunction "ID_4") (pintype "passive+no_connect"))
    )
    (net (code "52") (name "unconnected-(J29-Pad1)") (class "Default")
      (node (ref "J29") (pin "1") (pinfunction "1_1") (pintype "passive+no_connect"))
    )
    (net (code "53") (name "unconnected-(S3-PadMP1)") (class "Default")
      (node (ref "S3") (pin "MP1") (pinfunction "MP1_MP1") (pintype "passive+no_connect"))
    )
    (net (code "54") (name "unconnected-(S3-PadMP2)") (class "Default")
      (node (ref "S3") (pin "MP2") (pinfunction "MP2_MP2") (pintype "passive+no_connect"))
    )
    (net (code "55") (name "unconnected-(S3-PadMP3)") (class "Default")
      (node (ref "S3") (pin "MP3") (pinfunction "MP3_MP3") (pintype "passive+no_connect"))
    )
    (net (code "56") (name "unconnected-(S3-PadMP4)") (class "Default")
      (node (ref "S3") (pin "MP4") (pinfunction "MP4_MP4") (pintype "passive+no_connect"))
    )
    (net (code "57") (name "unconnected-(U11-P1.7{slash}TA1.0-Pad28)") (class "Default")
      (node (ref "U11") (pin "28") (pinfunction "P1.7/TA1.0_28") (pintype "bidirectional+no_connect"))
    )
    (net (code "58") (name "unconnected-(U11-P2.1{slash}TA1.2-Pad30)") (class "Default")
      (node (ref "U11") (pin "30") (pinfunction "P2.1/TA1.2_30") (pintype "bidirectional"))
    )
    (net (code "59") (name "unconnected-(U11-P2.2{slash}TA2CLK{slash}SMCLK-Pad31)") (class "Default")
      (node (ref "U11") (pin "31") (pinfunction "P2.2/TA2CLK/SMCLK_31") (pintype "bidirectional"))
    )
    (net (code "60") (name "unconnected-(U11-P2.3{slash}TA2.0-Pad32)") (class "Default")
      (node (ref "U11") (pin "32") (pinfunction "P2.3/TA2.0_32") (pintype "bidirectional"))
    )
    (net (code "61") (name "unconnected-(U11-P2.4{slash}TA2.1-Pad33)") (class "Default")
      (node (ref "U11") (pin "33") (pinfunction "P2.4/TA2.1_33") (pintype "bidirectional"))
    )
    (net (code "62") (name "unconnected-(U11-P2.5{slash}TA2.2-Pad34)") (class "Default")
      (node (ref "U11") (pin "34") (pinfunction "P2.5/TA2.2_34") (pintype "bidirectional"))
    )
    (net (code "63") (name "unconnected-(U11-P2.6{slash}RTCCLK{slash}DMAE0-Pad35)") (class "Default")
      (node (ref "U11") (pin "35") (pinfunction "P2.6/RTCCLK/DMAE0_35") (pintype "bidirectional"))
    )
    (net (code "64") (name "unconnected-(U11-P3.0{slash}UCB0SIMO{slash}UCB0SDA-Pad37)") (class "Default")
      (node (ref "U11") (pin "37") (pinfunction "P3.0/UCB0SIMO/UCB0SDA_37") (pintype "bidirectional+no_connect"))
    )
    (net (code "65") (name "unconnected-(U11-P3.1{slash}UCB0SOMI{slash}UCB0SCL-Pad38)") (class "Default")
      (node (ref "U11") (pin "38") (pinfunction "P3.1/UCB0SOMI/UCB0SCL_38") (pintype "bidirectional+no_connect"))
    )
    (net (code "66") (name "unconnected-(U11-P3.5{slash}TB0.5-Pad42)") (class "Default")
      (node (ref "U11") (pin "42") (pinfunction "P3.5/TB0.5_42") (pintype "bidirectional+no_connect"))
    )
    (net (code "67") (name "unconnected-(U11-P3.6{slash}TB0.6-Pad43)") (class "Default")
      (node (ref "U11") (pin "43") (pinfunction "P3.6/TB0.6_43") (pintype "bidirectional+no_connect"))
    )
    (net (code "68") (name "unconnected-(U11-P3.7{slash}TB0OUTH{slash}SVMOUT-Pad44)") (class "Default")
      (node (ref "U11") (pin "44") (pinfunction "P3.7/TB0OUTH/SVMOUT_44") (pintype "bidirectional+no_connect"))
    )
    (net (code "69") (name "unconnected-(U11-P4.0{slash}PM_UCB1STE{slash}PM_UCA1CLK-Pad45)") (class "Default")
      (node (ref "U11") (pin "45") (pinfunction "P4.0/PM_UCB1STE/PM_UCA1CLK_45") (pintype "bidirectional"))
    )
    (net (code "70") (name "unconnected-(U11-P4.1{slash}PM_UCB1SIMO{slash}PM_UCB1SDA-Pad46)") (class "Default")
      (node (ref "U11") (pin "46") (pinfunction "P4.1/PM_UCB1SIMO/PM_UCB1SDA_46") (pintype "bidirectional"))
    )
    (net (code "71") (name "unconnected-(U11-P5.0{slash}A8{slash}VREF+{slash}VEREF+-Pad9)") (class "Default")
      (node (ref "U11") (pin "9") (pinfunction "P5.0/A8/VREF+/VEREF+_9") (pintype "bidirectional+no_connect"))
    )
    (net (code "72") (name "unconnected-(U11-P5.1{slash}A9{slash}VREF-{slash}VEREF--Pad10)") (class "Default")
      (node (ref "U11") (pin "10") (pinfunction "P5.1/A9/VREF-/VEREF-_10") (pintype "bidirectional+no_connect"))
    )
    (net (code "73") (name "unconnected-(U11-P5.4{slash}XIN-Pad12)") (class "Default")
      (node (ref "U11") (pin "12") (pinfunction "P5.4/XIN_12") (pintype "bidirectional+no_connect"))
    )
    (net (code "74") (name "unconnected-(U11-P5.5{slash}XOUT-Pad13)") (class "Default")
      (node (ref "U11") (pin "13") (pinfunction "P5.5/XOUT_13") (pintype "bidirectional"))
    )
    (net (code "75") (name "unconnected-(U11-P5.6{slash}TB0.0-Pad55)") (class "Default")
      (node (ref "U11") (pin "55") (pinfunction "P5.6/TB0.0_55") (pintype "bidirectional+no_connect"))
    )
    (net (code "76") (name "unconnected-(U11-P5.7{slash}TB0.1-Pad56)") (class "Default")
      (node (ref "U11") (pin "56") (pinfunction "P5.7/TB0.1_56") (pintype "bidirectional+no_connect"))
    )
    (net (code "77") (name "unconnected-(U11-P6.0{slash}CB0{slash}A0-Pad77)") (class "Default")
      (node (ref "U11") (pin "77") (pinfunction "P6.0/CB0/A0_77") (pintype "bidirectional"))
    )
    (net (code "78") (name "unconnected-(U11-P6.1{slash}CB1{slash}A1-Pad78)") (class "Default")
      (node (ref "U11") (pin "78") (pinfunction "P6.1/CB1/A1_78") (pintype "bidirectional"))
    )
    (net (code "79") (name "unconnected-(U11-P6.2{slash}CB2{slash}A2-Pad79)") (class "Default")
      (node (ref "U11") (pin "79") (pinfunction "P6.2/CB2/A2_79") (pintype "bidirectional"))
    )
    (net (code "80") (name "unconnected-(U11-P6.3{slash}CB3{slash}A3-Pad80)") (class "Default")
      (node (ref "U11") (pin "80") (pinfunction "P6.3/CB3/A3_80") (pintype "bidirectional"))
    )
    (net (code "81") (name "unconnected-(U11-P6.4{slash}CB4{slash}A4-Pad1)") (class "Default")
      (node (ref "U11") (pin "1") (pinfunction "P6.4/CB4/A4_1") (pintype "bidirectional"))
    )
    (net (code "82") (name "unconnected-(U11-P6.5{slash}CB5{slash}A5-Pad2)") (class "Default")
      (node (ref "U11") (pin "2") (pinfunction "P6.5/CB5/A5_2") (pintype "bidirectional"))
    )
    (net (code "83") (name "unconnected-(U11-P6.6{slash}CB6{slash}A6-Pad3)") (class "Default")
      (node (ref "U11") (pin "3") (pinfunction "P6.6/CB6/A6_3") (pintype "bidirectional"))
    )
    (net (code "84") (name "unconnected-(U11-P6.7{slash}CB7{slash}A7-Pad4)") (class "Default")
      (node (ref "U11") (pin "4") (pinfunction "P6.7/CB7/A7_4") (pintype "bidirectional"))
    )
    (net (code "85") (name "unconnected-(U11-P7.0{slash}CB8{slash}A12-Pad5)") (class "Default")
      (node (ref "U11") (pin "5") (pinfunction "P7.0/CB8/A12_5") (pintype "bidirectional"))
    )
    (net (code "86") (name "unconnected-(U11-P7.1{slash}CB9{slash}A13-Pad6)") (class "Default")
      (node (ref "U11") (pin "6") (pinfunction "P7.1/CB9/A13_6") (pintype "bidirectional"))
    )
    (net (code "87") (name "unconnected-(U11-P7.2{slash}CB10{slash}A14-Pad7)") (class "Default")
      (node (ref "U11") (pin "7") (pinfunction "P7.2/CB10/A14_7") (pintype "bidirectional"))
    )
    (net (code "88") (name "unconnected-(U11-P7.3{slash}CB11{slash}A15-Pad8)") (class "Default")
      (node (ref "U11") (pin "8") (pinfunction "P7.3/CB11/A15_8") (pintype "bidirectional"))
    )
    (net (code "89") (name "unconnected-(U11-PJ.0{slash}TDO-Pad72)") (class "Default")
      (node (ref "U11") (pin "72") (pinfunction "PJ.0/TDO_72") (pintype "bidirectional"))
    )
    (net (code "90") (name "unconnected-(U11-PJ.1{slash}TDI{slash}TCLK-Pad73)") (class "Default")
      (node (ref "U11") (pin "73") (pinfunction "PJ.1/TDI/TCLK_73") (pintype "bidirectional"))
    )
    (net (code "91") (name "unconnected-(U11-PJ.2{slash}TMS-Pad74)") (class "Default")
      (node (ref "U11") (pin "74") (pinfunction "PJ.2/TMS_74") (pintype "bidirectional"))
    )
    (net (code "92") (name "unconnected-(U11-PJ.3{slash}TCK-Pad75)") (class "Default")
      (node (ref "U11") (pin "75") (pinfunction "PJ.3/TCK_75") (pintype "bidirectional"))
    )
    (net (code "93") (name "unconnected-(U14-NC-Pad4)") (class "Default")
      (node (ref "U14") (pin "4") (pinfunction "NC_4") (pintype "passive+no_connect"))
    )
  )
)
